# uC_mini_v2.net
KiCad netlist of a schematic drawn in EAGLE
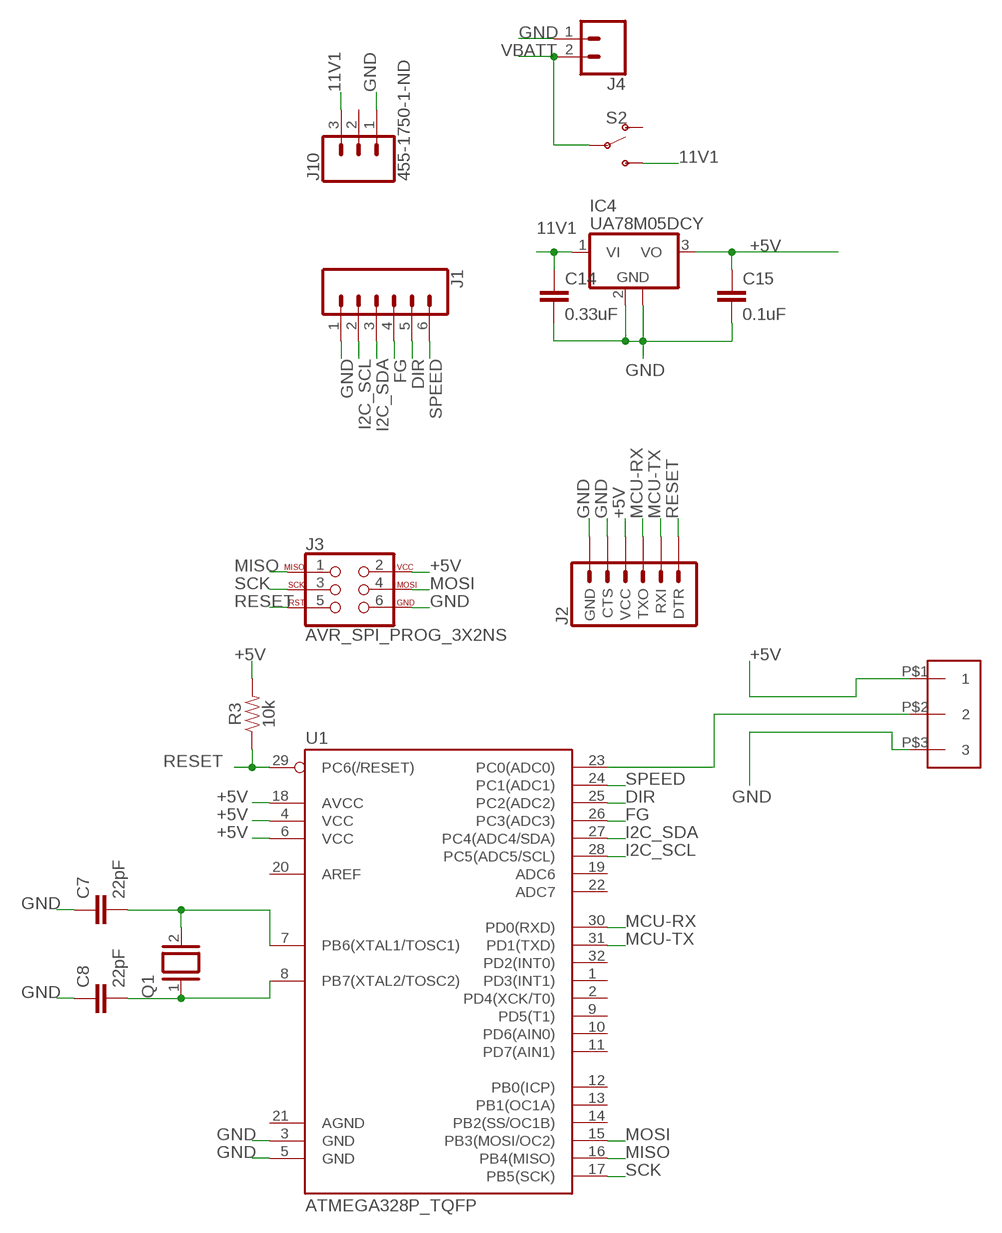
[diagram p0: schematic, sheet 1]

(export (version "E")
  (design (tool "Eeschema 10.0.6"))
  (components
    (comp (ref "C7")
      (value "22pF")
      (footprint "eagle-import:1206")
      (libsource (lib "eagle-import") (part "2.2UF-1206-50V-10%"))
    )
    (comp (ref "C8")
      (value "22pF")
      (footprint "eagle-import:1206")
      (libsource (lib "eagle-import") (part "2.2UF-1206-50V-10%"))
    )
    (comp (ref "C14")
      (value "0.33uF")
      (footprint "eagle-import:1206")
      (libsource (lib "eagle-import") (part "1.0UF-1206-50V-10%"))
    )
    (comp (ref "C15")
      (value "0.1uF")
      (footprint "eagle-import:1206")
      (libsource (lib "eagle-import") (part "1.0UF-1206-50V-10%"))
    )
    (comp (ref "IC4")
      (value "UA78M05DCY")
      (footprint "eagle-import:SOT223")
      (libsource (lib "eagle-import") (part "UA78MDCY05"))
    )
    (comp (ref "J1")
      (value "CONN_06LOCK")
      (footprint "eagle-import:1X06_LOCK")
      (libsource (lib "eagle-import") (part "CONN_06LOCK"))
    )
    (comp (ref "J2")
      (value "6_PIN_SERIAL_TARGET")
      (footprint "eagle-import:1X06")
      (libsource (lib "eagle-import") (part "6_PIN_SERIAL_TARGET"))
    )
    (comp (ref "J3")
      (value "AVR_SPI_PROG_3X2NS")
      (footprint "eagle-import:2X3-NS")
      (libsource (lib "eagle-import") (part "AVR_SPI_PROG_3X2NS"))
    )
    (comp (ref "J4")
      (value "CONN_02LOCK")
      (footprint "eagle-import:1X02_LOCK")
      (libsource (lib "eagle-import") (part "CONN_02LOCK"))
    )
    (comp (ref "J10")
      (value "455-1750-1-ND")
      (footprint "eagle-import:1X03")
      (libsource (lib "eagle-import") (part "CONN_03"))
    )
    (comp (ref "Q1")
      (value "XTAL/S")
      (footprint "eagle-import:QS")
      (libsource (lib "eagle-import") (part "XTAL/S"))
    )
    (comp (ref "R3")
      (value "10k")
      (footprint "eagle-import:1206")
      (libsource (lib "eagle-import") (part "RESISTOR1206"))
    )
    (comp (ref "S2")
      (value "SWITCH-SPDT-PTH-11.6X4.0MM")
      (footprint "eagle-import:SWITCH_SPDT_PTH_11.6X4.0MM")
      (libsource (lib "eagle-import") (part "SWITCH-SPDT-PTH-11.6X4.0MM"))
    )
    (comp (ref "U$3")
      (value "CONN_03_SMD_SMALL")
      (footprint "eagle-import:CONN_03_SMD_SMALL")
      (libsource (lib "eagle-import") (part "CONN_03_SMD_SMALL"))
    )
    (comp (ref "U1")
      (value "ATMEGA328P_TQFP")
      (footprint "eagle-import:TQFP32-08")
      (libsource (lib "eagle-import") (part "ATMEGA328P_TQFP"))
    )
  )
  (nets
    (net (code "1") (name "/+5V") (class "Default")
      (node (ref "C15") (pin "1") (pinfunction "1_1") (pintype "passive"))
      (node (ref "IC4") (pin "3") (pinfunction "VO_3") (pintype "passive"))
      (node (ref "J2") (pin "4") (pinfunction "VCC_4") (pintype "passive"))
      (node (ref "J3") (pin "2") (pinfunction "2_2") (pintype "passive"))
      (node (ref "R3") (pin "2") (pinfunction "2_2") (pintype "passive"))
      (node (ref "U$3") (pin "P$1") (pinfunction "1_P$1") (pintype "bidirectional"))
      (node (ref "U1") (pin "18") (pinfunction "AVCC_18") (pintype "bidirectional"))
      (node (ref "U1") (pin "4") (pinfunction "VCC_4") (pintype "bidirectional"))
      (node (ref "U1") (pin "6") (pinfunction "VCC_6") (pintype "bidirectional"))
    )
    (net (code "2") (name "/11V1") (class "Default")
      (node (ref "C14") (pin "1") (pinfunction "1_1") (pintype "passive"))
      (node (ref "IC4") (pin "1") (pinfunction "VI_1") (pintype "input"))
      (node (ref "J10") (pin "3") (pinfunction "3_3") (pintype "passive"))
      (node (ref "S2") (pin "3") (pinfunction "S_3") (pintype "passive"))
    )
    (net (code "3") (name "/DIR") (class "Default")
      (node (ref "J1") (pin "5") (pinfunction "5_5") (pintype "passive"))
      (node (ref "U1") (pin "25") (pinfunction "PC2(ADC2)_25") (pintype "bidirectional"))
    )
    (net (code "4") (name "/FG") (class "Default")
      (node (ref "J1") (pin "4") (pinfunction "4_4") (pintype "passive"))
      (node (ref "U1") (pin "26") (pinfunction "PC3(ADC3)_26") (pintype "bidirectional"))
    )
    (net (code "5") (name "/GND") (class "Default")
      (node (ref "C14") (pin "2") (pinfunction "2_2") (pintype "passive"))
      (node (ref "C15") (pin "2") (pinfunction "2_2") (pintype "passive"))
      (node (ref "C7") (pin "1") (pinfunction "1_1") (pintype "passive"))
      (node (ref "C8") (pin "1") (pinfunction "1_1") (pintype "passive"))
      (node (ref "IC4") (pin "2") (pinfunction "GND_2") (pintype "passive"))
      (node (ref "IC4") (pin "4") (pinfunction "GND_4") (pintype "passive"))
      (node (ref "J1") (pin "1") (pinfunction "1_1") (pintype "passive"))
      (node (ref "J10") (pin "1") (pinfunction "1_1") (pintype "passive"))
      (node (ref "J2") (pin "5") (pinfunction "CTS_5") (pintype "passive"))
      (node (ref "J2") (pin "6") (pinfunction "GND_6") (pintype "passive"))
      (node (ref "J3") (pin "6") (pinfunction "6_6") (pintype "passive"))
      (node (ref "J4") (pin "1") (pinfunction "1_1") (pintype "passive"))
      (node (ref "U$3") (pin "P$3") (pinfunction "3_P$3") (pintype "bidirectional"))
      (node (ref "U1") (pin "3") (pinfunction "GND_3") (pintype "bidirectional"))
      (node (ref "U1") (pin "5") (pinfunction "GND_5") (pintype "bidirectional"))
    )
    (net (code "6") (name "/I2C_SCL") (class "Default")
      (node (ref "J1") (pin "2") (pinfunction "2_2") (pintype "passive"))
      (node (ref "U1") (pin "28") (pinfunction "PC5(ADC5/SCL)_28") (pintype "bidirectional"))
    )
    (net (code "7") (name "/I2C_SDA") (class "Default")
      (node (ref "J1") (pin "3") (pinfunction "3_3") (pintype "passive"))
      (node (ref "U1") (pin "27") (pinfunction "PC4(ADC4/SDA)_27") (pintype "bidirectional"))
    )
    (net (code "8") (name "/MCU-RX") (class "Default")
      (node (ref "J2") (pin "3") (pinfunction "TXO_3") (pintype "passive"))
      (node (ref "U1") (pin "30") (pinfunction "PD0(RXD)_30") (pintype "bidirectional"))
    )
    (net (code "9") (name "/MCU-TX") (class "Default")
      (node (ref "J2") (pin "2") (pinfunction "RXI_2") (pintype "passive"))
      (node (ref "U1") (pin "31") (pinfunction "PD1(TXD)_31") (pintype "bidirectional"))
    )
    (net (code "10") (name "/MISO") (class "Default")
      (node (ref "J3") (pin "1") (pinfunction "1_1") (pintype "passive"))
      (node (ref "U1") (pin "16") (pinfunction "PB4(MISO)_16") (pintype "bidirectional"))
    )
    (net (code "11") (name "/MOSI") (class "Default")
      (node (ref "J3") (pin "4") (pinfunction "4_4") (pintype "passive"))
      (node (ref "U1") (pin "15") (pinfunction "PB3(MOSI/OC2)_15") (pintype "bidirectional"))
    )
    (net (code "12") (name "/RESET") (class "Default")
      (node (ref "J2") (pin "1") (pinfunction "DTR_1") (pintype "passive"))
      (node (ref "J3") (pin "5") (pinfunction "5_5") (pintype "passive"))
      (node (ref "R3") (pin "1") (pinfunction "1_1") (pintype "passive"))
      (node (ref "U1") (pin "29") (pinfunction "PC6(/RESET)_29") (pintype "bidirectional"))
    )
    (net (code "13") (name "/SCK") (class "Default")
      (node (ref "J3") (pin "3") (pinfunction "3_3") (pintype "passive"))
      (node (ref "U1") (pin "17") (pinfunction "PB5(SCK)_17") (pintype "bidirectional"))
    )
    (net (code "14") (name "/SPEED") (class "Default")
      (node (ref "J1") (pin "6") (pinfunction "6_6") (pintype "passive"))
      (node (ref "U1") (pin "24") (pinfunction "PC1(ADC1)_24") (pintype "bidirectional"))
    )
    (net (code "15") (name "/VBATT") (class "Default")
      (node (ref "J4") (pin "2") (pinfunction "2_2") (pintype "passive"))
      (node (ref "S2") (pin "2") (pinfunction "P_2") (pintype "passive"))
    )
    (net (code "16") (name "Net-(U$3-2)") (class "Default")
      (node (ref "U$3") (pin "P$2") (pinfunction "2_P$2") (pintype "bidirectional"))
      (node (ref "U1") (pin "23") (pinfunction "PC0(ADC0)_23") (pintype "bidirectional"))
    )
    (net (code "17") (name "Net-(U1-PB6(XTAL1{slash}TOSC1))") (class "Default")
      (node (ref "C7") (pin "2") (pinfunction "2_2") (pintype "passive"))
      (node (ref "Q1") (pin "2") (pinfunction "2_2") (pintype "passive"))
      (node (ref "U1") (pin "7") (pinfunction "PB6(XTAL1/TOSC1)_7") (pintype "bidirectional"))
    )
    (net (code "18") (name "Net-(U1-PB7(XTAL2{slash}TOSC2))") (class "Default")
      (node (ref "C8") (pin "2") (pinfunction "2_2") (pintype "passive"))
      (node (ref "Q1") (pin "1") (pinfunction "1_1") (pintype "passive"))
      (node (ref "U1") (pin "8") (pinfunction "PB7(XTAL2/TOSC2)_8") (pintype "bidirectional"))
    )
    (net (code "19") (name "unconnected-(J10-Pad2)") (class "Default")
      (node (ref "J10") (pin "2") (pinfunction "2_2") (pintype "passive"))
    )
    (net (code "20") (name "unconnected-(S2-O-Pad1)") (class "Default")
      (node (ref "S2") (pin "1") (pinfunction "O_1") (pintype "passive"))
    )
    (net (code "21") (name "unconnected-(U1-ADC6-Pad19)") (class "Default")
      (node (ref "U1") (pin "19") (pinfunction "ADC6_19") (pintype "bidirectional"))
    )
    (net (code "22") (name "unconnected-(U1-ADC7-Pad22)") (class "Default")
      (node (ref "U1") (pin "22") (pinfunction "ADC7_22") (pintype "bidirectional"))
    )
    (net (code "23") (name "unconnected-(U1-AGND-Pad21)") (class "Default")
      (node (ref "U1") (pin "21") (pinfunction "AGND_21") (pintype "bidirectional"))
    )
    (net (code "24") (name "unconnected-(U1-AREF-Pad20)") (class "Default")
      (node (ref "U1") (pin "20") (pinfunction "AREF_20") (pintype "bidirectional"))
    )
    (net (code "25") (name "unconnected-(U1-PB0(ICP)-Pad12)") (class "Default")
      (node (ref "U1") (pin "12") (pinfunction "PB0(ICP)_12") (pintype "bidirectional"))
    )
    (net (code "26") (name "unconnected-(U1-PB1(OC1A)-Pad13)") (class "Default")
      (node (ref "U1") (pin "13") (pinfunction "PB1(OC1A)_13") (pintype "bidirectional"))
    )
    (net (code "27") (name "unconnected-(U1-PB2(SS{slash}OC1B)-Pad14)") (class "Default")
      (node (ref "U1") (pin "14") (pinfunction "PB2(SS/OC1B)_14") (pintype "bidirectional"))
    )
    (net (code "28") (name "unconnected-(U1-PD2(INT0)-Pad32)") (class "Default")
      (node (ref "U1") (pin "32") (pinfunction "PD2(INT0)_32") (pintype "bidirectional"))
    )
    (net (code "29") (name "unconnected-(U1-PD3(INT1)-Pad1)") (class "Default")
      (node (ref "U1") (pin "1") (pinfunction "PD3(INT1)_1") (pintype "bidirectional"))
    )
    (net (code "30") (name "unconnected-(U1-PD4(XCK{slash}T0)-Pad2)") (class "Default")
      (node (ref "U1") (pin "2") (pinfunction "PD4(XCK/T0)_2") (pintype "bidirectional"))
    )
    (net (code "31") (name "unconnected-(U1-PD5(T1)-Pad9)") (class "Default")
      (node (ref "U1") (pin "9") (pinfunction "PD5(T1)_9") (pintype "bidirectional"))
    )
    (net (code "32") (name "unconnected-(U1-PD6(AIN0)-Pad10)") (class "Default")
      (node (ref "U1") (pin "10") (pinfunction "PD6(AIN0)_10") (pintype "bidirectional"))
    )
    (net (code "33") (name "unconnected-(U1-PD7(AIN1)-Pad11)") (class "Default")
      (node (ref "U1") (pin "11") (pinfunction "PD7(AIN1)_11") (pintype "bidirectional"))
    )
  )
)
